# lipo-max1811.net
KiCad netlist of a schematic drawn in EAGLE
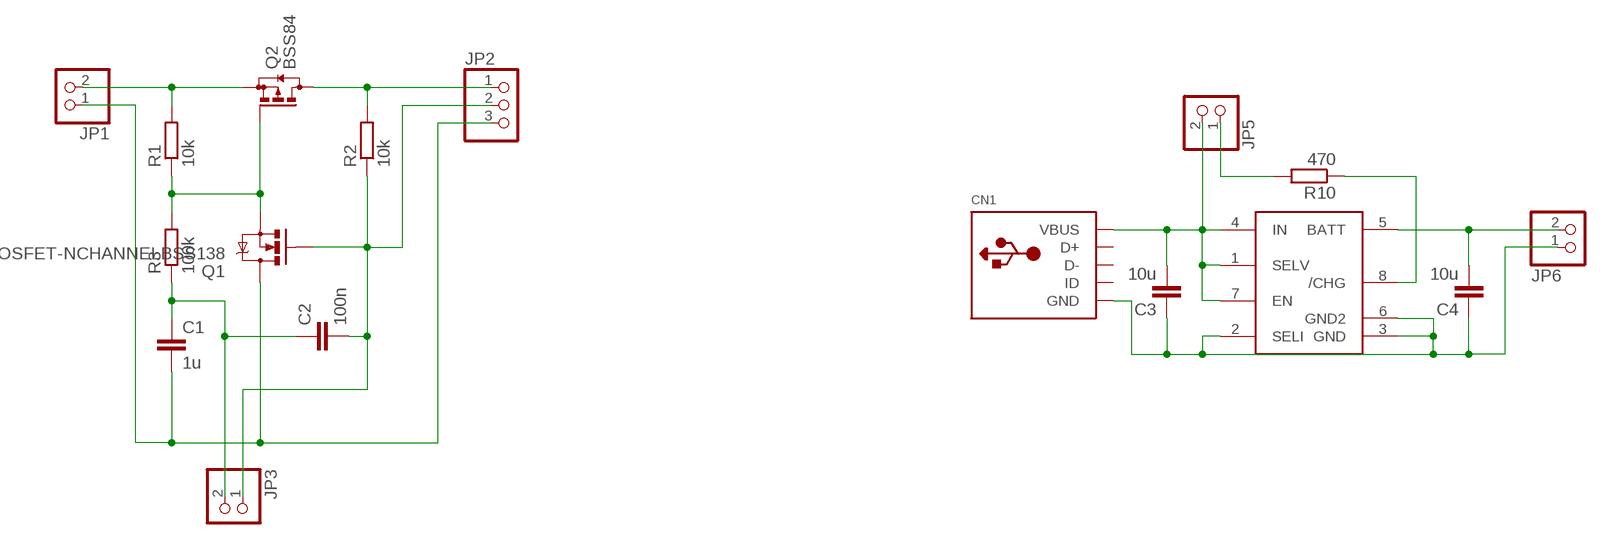
[diagram p0: schematic, sheet 1]

(export (version "E")
  (design (tool "Eeschema 10.0.6"))
  (components
    (comp (ref "C1")
      (value "1u")
      (footprint "eagle-import:C0805K")
      (libsource (lib "eagle-import") (part "C-EUC0805K"))
    )
    (comp (ref "C2")
      (value "100n")
      (footprint "eagle-import:C0805K")
      (libsource (lib "eagle-import") (part "C-EUC0805K"))
    )
    (comp (ref "C3")
      (value "10u")
      (footprint "eagle-import:C0805K")
      (libsource (lib "eagle-import") (part "C-EUC0805K"))
    )
    (comp (ref "C4")
      (value "10u")
      (footprint "eagle-import:C0805K")
      (libsource (lib "eagle-import") (part "C-EUC0805K"))
    )
    (comp (ref "CN1")
      (value "USBTHM")
      (footprint "eagle-import:USB-MINIB-THM")
      (libsource (lib "eagle-import") (part "USBTHM"))
    )
    (comp (ref "JP1")
      (value "PINHD-1X2")
      (footprint "eagle-import:1X02")
      (libsource (lib "eagle-import") (part "PINHD-1X2"))
    )
    (comp (ref "JP2")
      (value "PINHD-1X3")
      (footprint "eagle-import:1X03")
      (libsource (lib "eagle-import") (part "PINHD-1X3"))
    )
    (comp (ref "JP3")
      (value "PINHD-1X2")
      (footprint "eagle-import:1X02")
      (libsource (lib "eagle-import") (part "PINHD-1X2"))
    )
    (comp (ref "JP5")
      (value "PINHD-1X2")
      (footprint "eagle-import:1X02")
      (libsource (lib "eagle-import") (part "PINHD-1X2"))
    )
    (comp (ref "JP6")
      (value "PINHD-1X2")
      (footprint "eagle-import:1X02")
      (libsource (lib "eagle-import") (part "PINHD-1X2"))
    )
    (comp (ref "Q1")
      (value "MOSFET-NCHANNELBSS138")
      (footprint "eagle-import:SOT23")
      (libsource (lib "eagle-import") (part "MOSFET-NCHANNELBSS138"))
    )
    (comp (ref "Q2")
      (value "BSS84")
      (footprint "eagle-import:SOT23")
      (libsource (lib "eagle-import") (part "BSS84"))
    )
    (comp (ref "R1")
      (value "10k")
      (footprint "eagle-import:R0805")
      (libsource (lib "eagle-import") (part "R-EU_R0805"))
    )
    (comp (ref "R2")
      (value "10k")
      (footprint "eagle-import:M0805")
      (libsource (lib "eagle-import") (part "R-EU_M0805"))
    )
    (comp (ref "R3")
      (value "100k")
      (footprint "eagle-import:R0805")
      (libsource (lib "eagle-import") (part "R-EU_R0805"))
    )
    (comp (ref "R10")
      (value "470")
      (footprint "eagle-import:M0805")
      (libsource (lib "eagle-import") (part "R-EU_M0805"))
    )
    (comp (ref "U$1")
      (value "MAX1811SO8")
      (footprint "eagle-import:SO08")
      (libsource (lib "eagle-import") (part "MAX1811SO8"))
    )
  )
  (nets
    (net (code "1") (name "Net-(C1-Pad1)") (class "Default")
      (node (ref "C1") (pin "1") (pinfunction "1_1") (pintype "passive"))
      (node (ref "C2") (pin "1") (pinfunction "1_1") (pintype "passive"))
      (node (ref "JP3") (pin "2") (pinfunction "2_2") (pintype "passive"))
      (node (ref "R3") (pin "1") (pinfunction "1_1") (pintype "passive"))
    )
    (net (code "2") (name "Net-(JP5-Pad1)") (class "Default")
      (node (ref "JP5") (pin "1") (pinfunction "1_1") (pintype "passive"))
      (node (ref "R10") (pin "2") (pinfunction "2_2") (pintype "passive"))
    )
    (net (code "3") (name "Net-(Q1-D)") (class "Default")
      (node (ref "C1") (pin "2") (pinfunction "2_2") (pintype "passive"))
      (node (ref "JP1") (pin "1") (pinfunction "1_1") (pintype "passive"))
      (node (ref "JP2") (pin "3") (pinfunction "3_3") (pintype "passive"))
      (node (ref "Q1") (pin "3") (pinfunction "D_3") (pintype "passive"))
    )
    (net (code "4") (name "Net-(Q1-G)") (class "Default")
      (node (ref "C2") (pin "2") (pinfunction "2_2") (pintype "passive"))
      (node (ref "JP2") (pin "2") (pinfunction "2_2") (pintype "passive"))
      (node (ref "JP3") (pin "1") (pinfunction "1_1") (pintype "passive"))
      (node (ref "Q1") (pin "1") (pinfunction "G_1") (pintype "passive"))
      (node (ref "R2") (pin "1") (pinfunction "1_1") (pintype "passive"))
    )
    (net (code "5") (name "Net-(Q1-S)") (class "Default")
      (node (ref "Q1") (pin "2") (pinfunction "S_2") (pintype "passive"))
      (node (ref "Q2") (pin "1") (pinfunction "G_1") (pintype "passive"))
      (node (ref "R1") (pin "1") (pinfunction "1_1") (pintype "passive"))
      (node (ref "R3") (pin "2") (pinfunction "2_2") (pintype "passive"))
    )
    (net (code "6") (name "Net-(Q2-D)") (class "Default")
      (node (ref "JP2") (pin "1") (pinfunction "1_1") (pintype "passive"))
      (node (ref "Q2") (pin "3") (pinfunction "D_3") (pintype "passive"))
      (node (ref "R2") (pin "2") (pinfunction "2_2") (pintype "passive"))
    )
    (net (code "7") (name "Net-(Q2-S)") (class "Default")
      (node (ref "JP1") (pin "2") (pinfunction "2_2") (pintype "passive"))
      (node (ref "Q2") (pin "2") (pinfunction "S_2") (pintype "passive"))
      (node (ref "R1") (pin "2") (pinfunction "2_2") (pintype "passive"))
    )
    (net (code "8") (name "Net-(U$1-BATT)") (class "Default")
      (node (ref "C4") (pin "2") (pinfunction "2_2") (pintype "passive"))
      (node (ref "JP6") (pin "2") (pinfunction "2_2") (pintype "passive"))
      (node (ref "U$1") (pin "5") (pinfunction "BATT_5") (pintype "bidirectional"))
    )
    (net (code "9") (name "Net-(U$1-EN)") (class "Default")
      (node (ref "C3") (pin "2") (pinfunction "2_2") (pintype "passive"))
      (node (ref "CN1") (pin "VBUS") (pinfunction "VBUS_VBUS") (pintype "power_in"))
      (node (ref "JP5") (pin "2") (pinfunction "2_2") (pintype "passive"))
      (node (ref "U$1") (pin "1") (pinfunction "SELV_1") (pintype "bidirectional"))
      (node (ref "U$1") (pin "4") (pinfunction "IN_4") (pintype "bidirectional"))
      (node (ref "U$1") (pin "7") (pinfunction "EN_7") (pintype "bidirectional"))
    )
    (net (code "10") (name "Net-(U$1-GND)") (class "Default")
      (node (ref "C3") (pin "1") (pinfunction "1_1") (pintype "passive"))
      (node (ref "C4") (pin "1") (pinfunction "1_1") (pintype "passive"))
      (node (ref "CN1") (pin "GND") (pinfunction "GND_GND") (pintype "power_in"))
      (node (ref "JP6") (pin "1") (pinfunction "1_1") (pintype "passive"))
      (node (ref "U$1") (pin "2") (pinfunction "SELI_2") (pintype "bidirectional"))
      (node (ref "U$1") (pin "3") (pinfunction "GND_3") (pintype "bidirectional"))
      (node (ref "U$1") (pin "6") (pinfunction "GND2_6") (pintype "bidirectional"))
    )
    (net (code "11") (name "Net-(U$1-{slash}CHG)") (class "Default")
      (node (ref "R10") (pin "1") (pinfunction "1_1") (pintype "passive"))
      (node (ref "U$1") (pin "8") (pinfunction "/CHG_8") (pintype "bidirectional"))
    )
    (net (code "12") (name "unconnected-(CN1-PadD+)") (class "Default")
      (node (ref "CN1") (pin "D+") (pinfunction "D+_D+") (pintype "bidirectional"))
    )
    (net (code "13") (name "unconnected-(CN1-PadD-)") (class "Default")
      (node (ref "CN1") (pin "D-") (pinfunction "D-_D-") (pintype "bidirectional"))
    )
    (net (code "14") (name "unconnected-(CN1-PadID)") (class "Default")
      (node (ref "CN1") (pin "ID") (pinfunction "ID_ID") (pintype "bidirectional"))
    )
  )
)
